# Pyros.net
KiCad netlist of a schematic drawn in Altium Designer
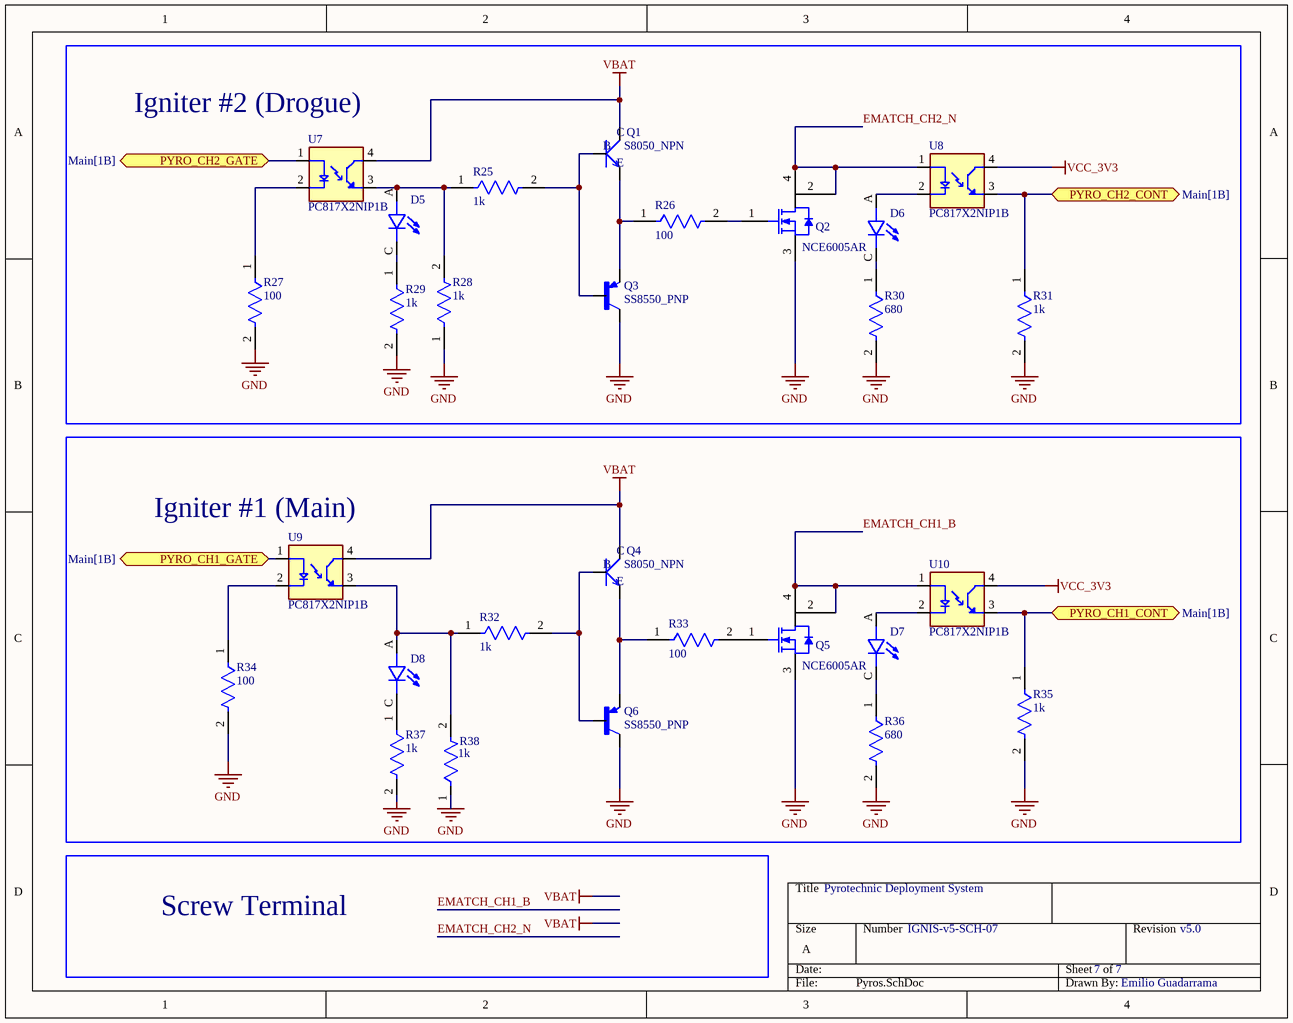
[diagram p0: Pyros.SchDoc]

(export (version "E")
  (design (tool "Eeschema 10.0.6"))
  (components
    (comp (ref "D5")
      (value "SML-LXT0805IW-TR")
      (footprint "LEDC2012X120N")
      (fields (field (name "MF") "Lumex Opto/Components"))
      (libsource (lib "LED_0805-SML-LXT0805IW-TR") (part "SML-LXT0805IW-TR"))
    )
    (comp (ref "D6")
      (value "SML-LXT0805IW-TR")
      (footprint "LEDC2012X120N")
      (fields (field (name "MF") "Lumex Opto/Components"))
      (libsource (lib "LED_0805-SML-LXT0805IW-TR") (part "SML-LXT0805IW-TR"))
    )
    (comp (ref "D7")
      (value "SML-LXT0805IW-TR")
      (footprint "LEDC2012X120N")
      (fields (field (name "MF") "Lumex Opto/Components"))
      (libsource (lib "LED_0805-SML-LXT0805IW-TR") (part "SML-LXT0805IW-TR"))
    )
    (comp (ref "D8")
      (value "SML-LXT0805IW-TR")
      (footprint "LEDC2012X120N")
      (fields (field (name "MF") "Lumex Opto/Components"))
      (libsource (lib "LED_0805-SML-LXT0805IW-TR") (part "SML-LXT0805IW-TR"))
    )
    (comp (ref "Q1")
      (value "S8050_NPN")
      (footprint "SOT-23")
      (description "Bipolar (BJT) Transistor NPN 25 V 500 mA 150MHz 300 mW Surface Mount SOT-23")
      (fields (field (name "MF") "UMW") (field (name "MP") "S8050"))
      (libsource (lib "S8050") (part "SMD-TRANSISTORS-NPN-25V-500MW(SOT-23)"))
    )
    (comp (ref "Q2")
      (value "NCE6005AR")
      (footprint "PCBComponent_1")
      (libsource (lib "NCE6005AR_Mosfet_N") (part "NCE6005AR"))
    )
    (comp (ref "Q3")
      (value "SS8550_PNP")
      (footprint "SOT95P252X140-3N")
      (description "Bipolar (BJT) Transistor PNP 25 V 1.5 A 100MHz 300 mW Surface Mount SOT-23")
      (fields (field (name "MF") "MDD") (field (name "MP") "SS8550"))
      (libsource (lib "SS8550") (part "SS8550"))
    )
    (comp (ref "Q4")
      (value "S8050_NPN")
      (footprint "SOT-23")
      (description "Bipolar (BJT) Transistor NPN 25 V 500 mA 150MHz 300 mW Surface Mount SOT-23")
      (fields (field (name "MF") "UMW") (field (name "MP") "S8050"))
      (libsource (lib "S8050") (part "SMD-TRANSISTORS-NPN-25V-500MW(SOT-23)"))
    )
    (comp (ref "Q5")
      (value "NCE6005AR")
      (footprint "PCBComponent_1")
      (libsource (lib "NCE6005AR_Mosfet_N") (part "NCE6005AR"))
    )
    (comp (ref "Q6")
      (value "SS8550_PNP")
      (footprint "SOT95P252X140-3N")
      (description "Bipolar (BJT) Transistor PNP 25 V 1.5 A 100MHz 300 mW Surface Mount SOT-23")
      (fields (field (name "MF") "MDD") (field (name "MP") "SS8550"))
      (libsource (lib "SS8550") (part "SS8550"))
    )
    (comp (ref "R25")
      (value "1k")
      (footprint "FP-MCT0603-IPC_A")
      (description "RES SMD 100 OHM 1% 1/8W 0603")
      (fields (field (name "TOLERANCE") "0.1%"))
      (libsource (lib "Altium Content Vault") (part "1029c3af85768c4190bb7ad29bc67b5"))
    )
    (comp (ref "R26")
      (value "100")
      (footprint "FP-MCT0603-IPC_A")
      (description "RES SMD 100 OHM 1% 1/8W 0603")
      (fields (field (name "TOLERANCE") "0.1%"))
      (libsource (lib "Altium Content Vault") (part "1029c3af85768c4190bb7ad29bc67b5"))
    )
    (comp (ref "R27")
      (value "100")
      (footprint "FP-MCT0603-IPC_A")
      (description "RES SMD 100 OHM 1% 1/8W 0603")
      (fields (field (name "TOLERANCE") "0.1%"))
      (libsource (lib "Altium Content Vault") (part "1029c3af85768c4190bb7ad29bc67b5"))
    )
    (comp (ref "R28")
      (value "1k")
      (footprint "FP-MCT0603-IPC_A")
      (description "RES SMD 100 OHM 1% 1/8W 0603")
      (fields (field (name "TOLERANCE") "0.1%"))
      (libsource (lib "Altium Content Vault") (part "1029c3af85768c4190bb7ad29bc67b5"))
    )
    (comp (ref "R29")
      (value "1k")
      (footprint "FP-MCT0603-IPC_A")
      (description "RES SMD 100 OHM 1% 1/8W 0603")
      (fields (field (name "TOLERANCE") "0.1%"))
      (libsource (lib "Altium Content Vault") (part "1029c3af85768c4190bb7ad29bc67b5"))
    )
    (comp (ref "R30")
      (value "680")
      (footprint "FP-MCT0603-IPC_A")
      (description "RES SMD 100 OHM 1% 1/8W 0603")
      (fields (field (name "TOLERANCE") "0.1%"))
      (libsource (lib "Altium Content Vault") (part "1029c3af85768c4190bb7ad29bc67b5"))
    )
    (comp (ref "R31")
      (value "1k")
      (footprint "FP-MCT0603-IPC_A")
      (description "RES SMD 100 OHM 1% 1/8W 0603")
      (fields (field (name "TOLERANCE") "0.1%"))
      (libsource (lib "Altium Content Vault") (part "1029c3af85768c4190bb7ad29bc67b5"))
    )
    (comp (ref "R32")
      (value "1k")
      (footprint "FP-MCT0603-IPC_A")
      (description "RES SMD 100 OHM 1% 1/8W 0603")
      (fields (field (name "TOLERANCE") "0.1%"))
      (libsource (lib "Altium Content Vault") (part "1029c3af85768c4190bb7ad29bc67b5"))
    )
    (comp (ref "R33")
      (value "100")
      (footprint "FP-MCT0603-IPC_A")
      (description "RES SMD 100 OHM 1% 1/8W 0603")
      (fields (field (name "TOLERANCE") "0.1%"))
      (libsource (lib "Altium Content Vault") (part "1029c3af85768c4190bb7ad29bc67b5"))
    )
    (comp (ref "R34")
      (value "100")
      (footprint "FP-MCT0603-IPC_A")
      (description "RES SMD 100 OHM 1% 1/8W 0603")
      (fields (field (name "TOLERANCE") "0.1%"))
      (libsource (lib "Altium Content Vault") (part "1029c3af85768c4190bb7ad29bc67b5"))
    )
    (comp (ref "R35")
      (value "1k")
      (footprint "FP-MCT0603-IPC_A")
      (description "RES SMD 100 OHM 1% 1/8W 0603")
      (fields (field (name "TOLERANCE") "0.1%"))
      (libsource (lib "Altium Content Vault") (part "1029c3af85768c4190bb7ad29bc67b5"))
    )
    (comp (ref "R36")
      (value "680")
      (footprint "FP-MCT0603-IPC_A")
      (description "RES SMD 100 OHM 1% 1/8W 0603")
      (fields (field (name "TOLERANCE") "0.1%"))
      (libsource (lib "Altium Content Vault") (part "1029c3af85768c4190bb7ad29bc67b5"))
    )
    (comp (ref "R37")
      (value "1k")
      (footprint "FP-MCT0603-IPC_A")
      (description "RES SMD 100 OHM 1% 1/8W 0603")
      (fields (field (name "TOLERANCE") "0.1%"))
      (libsource (lib "Altium Content Vault") (part "1029c3af85768c4190bb7ad29bc67b5"))
    )
    (comp (ref "R38")
      (value "1k")
      (footprint "FP-MCT0603-IPC_A")
      (description "RES SMD 100 OHM 1% 1/8W 0603")
      (fields (field (name "TOLERANCE") "0.1%"))
      (libsource (lib "Altium Content Vault") (part "1029c3af85768c4190bb7ad29bc67b5"))
    )
    (comp (ref "U7")
      (value "PC817X2NIP1B")
      (footprint "SOIC254P960X420-4N")
      (description "Optocoupler DC-IN 1-CH Transistor DC-OUT 4-Pin DIP SMD T/R")
      (fields (field (name "MF") "Sharp Microelectronics"))
      (libsource (lib "PC817X2NIP1B") (part "PC817X2NIP1B"))
    )
    (comp (ref "U8")
      (value "PC817X2NIP1B")
      (footprint "SOIC254P960X420-4N")
      (description "Optocoupler DC-IN 1-CH Transistor DC-OUT 4-Pin DIP SMD T/R")
      (fields (field (name "MF") "Sharp Microelectronics"))
      (libsource (lib "PC817X2NIP1B") (part "PC817X2NIP1B"))
    )
    (comp (ref "U9")
      (value "PC817X2NIP1B")
      (footprint "SOIC254P960X420-4N")
      (description "Optocoupler DC-IN 1-CH Transistor DC-OUT 4-Pin DIP SMD T/R")
      (fields (field (name "MF") "Sharp Microelectronics"))
      (libsource (lib "Optoisolator-PC817X2NIP1B") (part "PC817X2NIP1B"))
    )
    (comp (ref "U10")
      (value "PC817X2NIP1B")
      (footprint "SOIC254P960X420-4N")
      (description "Optocoupler DC-IN 1-CH Transistor DC-OUT 4-Pin DIP SMD T/R")
      (fields (field (name "MF") "Sharp Microelectronics"))
      (libsource (lib "Optoisolator-PC817X2NIP1B") (part "PC817X2NIP1B"))
    )
  )
  (nets
    (net (code "1") (name "/EMATCH_CH1_B") (class "Default")
      (node (ref "Q5") (pin "2") (pinfunction "D_2") (pintype "passive"))
      (node (ref "Q5") (pin "4") (pinfunction "D_4") (pintype "passive"))
      (node (ref "U10") (pin "1") (pinfunction "A_1") (pintype "passive"))
    )
    (net (code "2") (name "/EMATCH_CH2_N") (class "Default")
      (node (ref "Q2") (pin "2") (pinfunction "D_2") (pintype "passive"))
      (node (ref "Q2") (pin "4") (pinfunction "D_4") (pintype "passive"))
      (node (ref "U8") (pin "1") (pinfunction "A_1") (pintype "passive"))
    )
    (net (code "3") (name "/PYRO_CH1_CONT") (class "Default")
      (node (ref "R35") (pin "1") (pinfunction "1_1") (pintype "passive"))
      (node (ref "U10") (pin "3") (pinfunction "ET_3") (pintype "passive"))
    )
    (net (code "4") (name "/PYRO_CH1_GATE") (class "Default")
      (node (ref "U9") (pin "1") (pinfunction "A_1") (pintype "passive"))
    )
    (net (code "5") (name "/PYRO_CH2_CONT") (class "Default")
      (node (ref "R31") (pin "1") (pinfunction "1_1") (pintype "passive"))
      (node (ref "U8") (pin "3") (pinfunction "ET_3") (pintype "passive"))
    )
    (net (code "6") (name "/PYRO_CH2_GATE") (class "Default")
      (node (ref "U7") (pin "1") (pinfunction "A_1") (pintype "passive"))
    )
    (net (code "7") (name "GND") (class "Default")
      (node (ref "Q2") (pin "3") (pinfunction "S_3") (pintype "passive"))
      (node (ref "Q3") (pin "3") (pinfunction "C_3") (pintype "passive"))
      (node (ref "Q5") (pin "3") (pinfunction "S_3") (pintype "passive"))
      (node (ref "Q6") (pin "3") (pinfunction "C_3") (pintype "passive"))
      (node (ref "R27") (pin "2") (pinfunction "2_2") (pintype "passive"))
      (node (ref "R28") (pin "1") (pinfunction "1_1") (pintype "passive"))
      (node (ref "R29") (pin "2") (pinfunction "2_2") (pintype "passive"))
      (node (ref "R30") (pin "2") (pinfunction "2_2") (pintype "passive"))
      (node (ref "R31") (pin "2") (pinfunction "2_2") (pintype "passive"))
      (node (ref "R34") (pin "2") (pinfunction "2_2") (pintype "passive"))
      (node (ref "R35") (pin "2") (pinfunction "2_2") (pintype "passive"))
      (node (ref "R36") (pin "2") (pinfunction "2_2") (pintype "passive"))
      (node (ref "R37") (pin "2") (pinfunction "2_2") (pintype "passive"))
      (node (ref "R38") (pin "1") (pinfunction "1_1") (pintype "passive"))
    )
    (net (code "8") (name "Net-(D5-PadC)") (class "Default")
      (node (ref "D5") (pin "C") (pinfunction "C_C") (pintype "passive"))
      (node (ref "R29") (pin "1") (pinfunction "1_1") (pintype "passive"))
    )
    (net (code "9") (name "Net-(D6-PadC)") (class "Default")
      (node (ref "D6") (pin "C") (pinfunction "C_C") (pintype "passive"))
      (node (ref "R30") (pin "1") (pinfunction "1_1") (pintype "passive"))
    )
    (net (code "10") (name "Net-(D7-PadC)") (class "Default")
      (node (ref "D7") (pin "C") (pinfunction "C_C") (pintype "passive"))
      (node (ref "R36") (pin "1") (pinfunction "1_1") (pintype "passive"))
    )
    (net (code "11") (name "Net-(D8-PadC)") (class "Default")
      (node (ref "D8") (pin "C") (pinfunction "C_C") (pintype "passive"))
      (node (ref "R37") (pin "1") (pinfunction "1_1") (pintype "passive"))
    )
    (net (code "12") (name "Net-(Q1-B)") (class "Default")
      (node (ref "Q1") (pin "1") (pinfunction "B_1") (pintype "passive"))
      (node (ref "Q3") (pin "1") (pinfunction "B_1") (pintype "passive"))
      (node (ref "R25") (pin "2") (pinfunction "2_2") (pintype "passive"))
    )
    (net (code "13") (name "Net-(Q1-E)") (class "Default")
      (node (ref "Q1") (pin "2") (pinfunction "E_2") (pintype "passive"))
      (node (ref "Q3") (pin "2") (pinfunction "E_2") (pintype "passive"))
      (node (ref "R26") (pin "1") (pinfunction "1_1") (pintype "passive"))
    )
    (net (code "14") (name "Net-(Q2-G)") (class "Default")
      (node (ref "Q2") (pin "1") (pinfunction "G_1") (pintype "passive"))
      (node (ref "R26") (pin "2") (pinfunction "2_2") (pintype "passive"))
    )
    (net (code "15") (name "Net-(Q4-B)") (class "Default")
      (node (ref "Q4") (pin "1") (pinfunction "B_1") (pintype "passive"))
      (node (ref "Q6") (pin "1") (pinfunction "B_1") (pintype "passive"))
      (node (ref "R32") (pin "2") (pinfunction "2_2") (pintype "passive"))
    )
    (net (code "16") (name "Net-(Q4-E)") (class "Default")
      (node (ref "Q4") (pin "2") (pinfunction "E_2") (pintype "passive"))
      (node (ref "Q6") (pin "2") (pinfunction "E_2") (pintype "passive"))
      (node (ref "R33") (pin "1") (pinfunction "1_1") (pintype "passive"))
    )
    (net (code "17") (name "Net-(Q5-G)") (class "Default")
      (node (ref "Q5") (pin "1") (pinfunction "G_1") (pintype "passive"))
      (node (ref "R33") (pin "2") (pinfunction "2_2") (pintype "passive"))
    )
    (net (code "18") (name "Net-(U7-C)") (class "Default")
      (node (ref "R27") (pin "1") (pinfunction "1_1") (pintype "passive"))
      (node (ref "U7") (pin "2") (pinfunction "C_2") (pintype "passive"))
    )
    (net (code "19") (name "Net-(U7-ET)") (class "Default")
      (node (ref "D5") (pin "A") (pinfunction "A_A") (pintype "passive"))
      (node (ref "R25") (pin "1") (pinfunction "1_1") (pintype "passive"))
      (node (ref "R28") (pin "2") (pinfunction "2_2") (pintype "passive"))
      (node (ref "U7") (pin "3") (pinfunction "ET_3") (pintype "passive"))
    )
    (net (code "20") (name "Net-(U8-C)") (class "Default")
      (node (ref "D6") (pin "A") (pinfunction "A_A") (pintype "passive"))
      (node (ref "U8") (pin "2") (pinfunction "C_2") (pintype "passive"))
    )
    (net (code "21") (name "Net-(U9-C)") (class "Default")
      (node (ref "R34") (pin "1") (pinfunction "1_1") (pintype "passive"))
      (node (ref "U9") (pin "2") (pinfunction "C_2") (pintype "passive"))
    )
    (net (code "22") (name "Net-(U9-ET)") (class "Default")
      (node (ref "D8") (pin "A") (pinfunction "A_A") (pintype "passive"))
      (node (ref "R32") (pin "1") (pinfunction "1_1") (pintype "passive"))
      (node (ref "R38") (pin "2") (pinfunction "2_2") (pintype "passive"))
      (node (ref "U9") (pin "3") (pinfunction "ET_3") (pintype "passive"))
    )
    (net (code "23") (name "Net-(U10-C)") (class "Default")
      (node (ref "D7") (pin "A") (pinfunction "A_A") (pintype "passive"))
      (node (ref "U10") (pin "2") (pinfunction "C_2") (pintype "passive"))
    )
    (net (code "24") (name "VBAT") (class "Default")
      (node (ref "Q1") (pin "3") (pinfunction "C_3") (pintype "passive"))
      (node (ref "Q4") (pin "3") (pinfunction "C_3") (pintype "passive"))
      (node (ref "U7") (pin "4") (pinfunction "CT_4") (pintype "passive"))
      (node (ref "U9") (pin "4") (pinfunction "CT_4") (pintype "passive"))
    )
    (net (code "25") (name "VCC_3V3") (class "Default")
      (node (ref "U10") (pin "4") (pinfunction "CT_4") (pintype "passive"))
      (node (ref "U8") (pin "4") (pinfunction "CT_4") (pintype "passive"))
    )
  )
)
